# CPU_-_Communications.net
KiCad netlist of a schematic drawn in Altium Designer
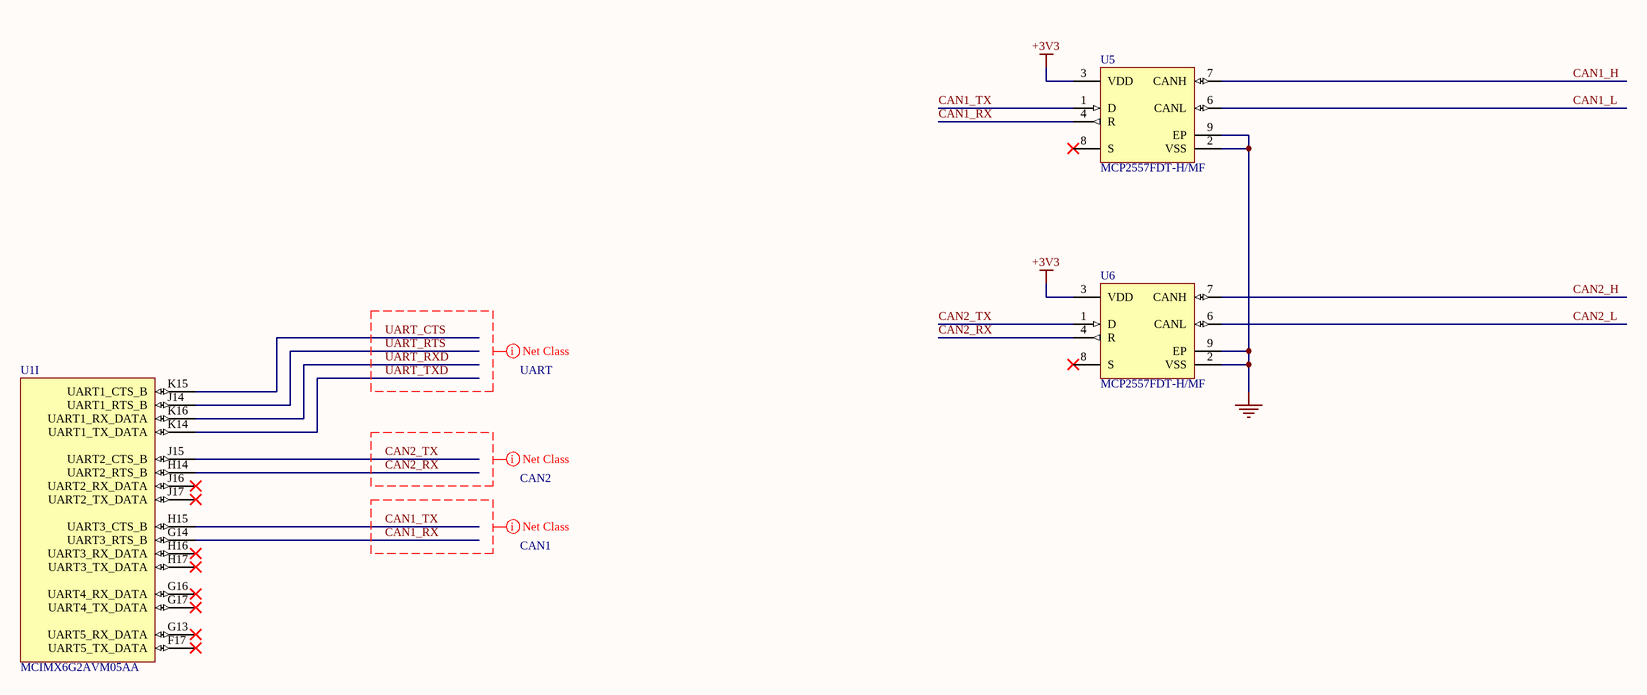
[diagram p0: CPU - Communications.SchDoc]

(export (version "E")
  (design (tool "Eeschema 10.0.6"))
  (components
    (comp (ref "U1")
      (value "MCIMX6G2AVM05AA")
      (footprint "BGA289C80P17X17_1400X1400X132")
      (libsource (lib "Hub-UV17") (part "MCIMX6G2AVM05AA"))
    )
    (comp (ref "U5")
      (value "MCP2557FDT-H/MF")
      (footprint "QFN65P300X300X90_HS-9N")
      (description "CAN transceiver")
      (libsource (lib "CDU") (part "MCP2557FDT-H/MF"))
    )
    (comp (ref "U6")
      (value "MCP2557FDT-H/MF")
      (footprint "QFN65P300X300X90_HS-9N")
      (description "CAN transceiver")
      (libsource (lib "CDU") (part "MCP2557FDT-H/MF"))
    )
  )
  (nets
    (net (code "1") (name "+3V3") (class "Default")
      (node (ref "U5") (pin "3") (pinfunction "VDD_3") (pintype "power_in"))
      (node (ref "U6") (pin "3") (pinfunction "VDD_3") (pintype "power_in"))
    )
    (net (code "2") (name "/CAN1_H") (class "Default")
      (node (ref "U5") (pin "7") (pinfunction "CANH_7") (pintype "bidirectional"))
    )
    (net (code "3") (name "/CAN1_L") (class "Default")
      (node (ref "U5") (pin "6") (pinfunction "CANL_6") (pintype "bidirectional"))
    )
    (net (code "4") (name "/CAN1_RX") (class "Default")
      (node (ref "U1") (pin "G14") (pinfunction "UART3_RTS_B_G14") (pintype "bidirectional"))
      (node (ref "U5") (pin "4") (pinfunction "R_4") (pintype "output"))
    )
    (net (code "5") (name "/CAN1_TX") (class "Default")
      (node (ref "U1") (pin "H15") (pinfunction "UART3_CTS_B_H15") (pintype "bidirectional"))
      (node (ref "U5") (pin "1") (pinfunction "D_1") (pintype "input"))
    )
    (net (code "6") (name "/CAN2_H") (class "Default")
      (node (ref "U6") (pin "7") (pinfunction "CANH_7") (pintype "bidirectional"))
    )
    (net (code "7") (name "/CAN2_L") (class "Default")
      (node (ref "U6") (pin "6") (pinfunction "CANL_6") (pintype "bidirectional"))
    )
    (net (code "8") (name "/CAN2_RX") (class "Default")
      (node (ref "U1") (pin "H14") (pinfunction "UART2_RTS_B_H14") (pintype "bidirectional"))
      (node (ref "U6") (pin "4") (pinfunction "R_4") (pintype "output"))
    )
    (net (code "9") (name "/CAN2_TX") (class "Default")
      (node (ref "U1") (pin "J15") (pinfunction "UART2_CTS_B_J15") (pintype "bidirectional"))
      (node (ref "U6") (pin "1") (pinfunction "D_1") (pintype "input"))
    )
    (net (code "10") (name "/UART_CTS") (class "Default")
      (node (ref "U1") (pin "K15") (pinfunction "UART1_CTS_B_K15") (pintype "bidirectional"))
    )
    (net (code "11") (name "/UART_RTS") (class "Default")
      (node (ref "U1") (pin "J14") (pinfunction "UART1_RTS_B_J14") (pintype "bidirectional"))
    )
    (net (code "12") (name "/UART_RXD") (class "Default")
      (node (ref "U1") (pin "K16") (pinfunction "UART1_RX_DATA_K16") (pintype "bidirectional"))
    )
    (net (code "13") (name "/UART_TXD") (class "Default")
      (node (ref "U1") (pin "K14") (pinfunction "UART1_TX_DATA_K14") (pintype "bidirectional"))
    )
    (net (code "14") (name "GND") (class "Default")
      (node (ref "U5") (pin "2") (pinfunction "VSS_2") (pintype "power_in"))
      (node (ref "U5") (pin "9") (pinfunction "EP_9") (pintype "power_in"))
      (node (ref "U6") (pin "2") (pinfunction "VSS_2") (pintype "power_in"))
      (node (ref "U6") (pin "9") (pinfunction "EP_9") (pintype "power_in"))
    )
    (net (code "15") (name "unconnected-(U1I-UART2_RX_DATA-PadJ16)") (class "Default")
      (node (ref "U1") (pin "J16") (pinfunction "UART2_RX_DATA_J16") (pintype "bidirectional+no_connect"))
    )
    (net (code "16") (name "unconnected-(U1I-UART2_TX_DATA-PadJ17)") (class "Default")
      (node (ref "U1") (pin "J17") (pinfunction "UART2_TX_DATA_J17") (pintype "bidirectional+no_connect"))
    )
    (net (code "17") (name "unconnected-(U1I-UART3_RX_DATA-PadH16)") (class "Default")
      (node (ref "U1") (pin "H16") (pinfunction "UART3_RX_DATA_H16") (pintype "bidirectional+no_connect"))
    )
    (net (code "18") (name "unconnected-(U1I-UART3_TX_DATA-PadH17)") (class "Default")
      (node (ref "U1") (pin "H17") (pinfunction "UART3_TX_DATA_H17") (pintype "bidirectional+no_connect"))
    )
    (net (code "19") (name "unconnected-(U1I-UART4_RX_DATA-PadG16)") (class "Default")
      (node (ref "U1") (pin "G16") (pinfunction "UART4_RX_DATA_G16") (pintype "bidirectional+no_connect"))
    )
    (net (code "20") (name "unconnected-(U1I-UART4_TX_DATA-PadG17)") (class "Default")
      (node (ref "U1") (pin "G17") (pinfunction "UART4_TX_DATA_G17") (pintype "bidirectional+no_connect"))
    )
    (net (code "21") (name "unconnected-(U1I-UART5_RX_DATA-PadG13)") (class "Default")
      (node (ref "U1") (pin "G13") (pinfunction "UART5_RX_DATA_G13") (pintype "bidirectional+no_connect"))
    )
    (net (code "22") (name "unconnected-(U1I-UART5_TX_DATA-PadF17)") (class "Default")
      (node (ref "U1") (pin "F17") (pinfunction "UART5_TX_DATA_F17") (pintype "bidirectional+no_connect"))
    )
    (net (code "23") (name "unconnected-(U5-NC-Pad5)") (class "Default")
      (node (ref "U5") (pin "5") (pinfunction "NC_5") (pintype "passive"))
    )
    (net (code "24") (name "unconnected-(U5-S-Pad8)") (class "Default")
      (node (ref "U5") (pin "8") (pinfunction "S_8") (pintype "passive+no_connect"))
    )
    (net (code "25") (name "unconnected-(U6-NC-Pad5)") (class "Default")
      (node (ref "U6") (pin "5") (pinfunction "NC_5") (pintype "passive"))
    )
    (net (code "26") (name "unconnected-(U6-S-Pad8)") (class "Default")
      (node (ref "U6") (pin "8") (pinfunction "S_8") (pintype "passive+no_connect"))
    )
  )
)
